# fuse_board.net
KiCad netlist of a schematic drawn in EAGLE
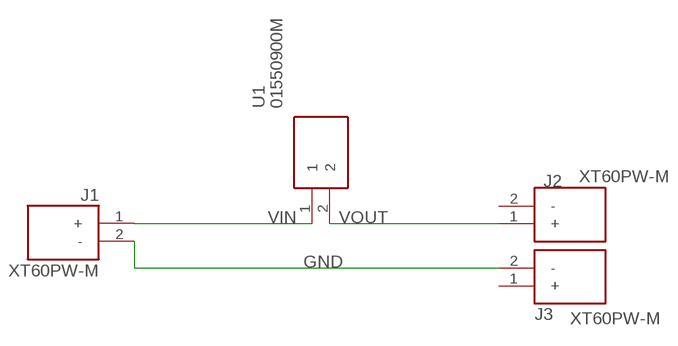
[diagram p0: schematic, sheet 1]

(export (version "E")
  (design (tool "Eeschema 10.0.6"))
  (components
    (comp (ref "J1")
      (value "XT60PW-M")
      (footprint "eagle-import:AMASS_XT60PW-M")
      (fields (field (name "MF") "AMASS"))
      (libsource (lib "eagle-import") (part "XT60PW-M"))
    )
    (comp (ref "J2")
      (value "XT60PW-M")
      (footprint "eagle-import:AMASS_XT60PW-M")
      (fields (field (name "MF") "AMASS"))
      (libsource (lib "eagle-import") (part "XT60PW-M"))
    )
    (comp (ref "J3")
      (value "XT60PW-M")
      (footprint "eagle-import:AMASS_XT60PW-M")
      (fields (field (name "MF") "AMASS"))
      (libsource (lib "eagle-import") (part "XT60PW-M"))
    )
    (comp (ref "U1")
      (value "01550900M")
      (footprint "eagle-import:0154.250DR")
      (fields (field (name "MOUSER_PART_NUMBER") "576-01550900M"))
      (libsource (lib "eagle-import") (part "01550900M"))
    )
  )
  (nets
    (net (code "1") (name "/GND") (class "Default")
      (node (ref "J1") (pin "2") (pinfunction "-_2") (pintype "passive"))
      (node (ref "J3") (pin "2") (pinfunction "-_2") (pintype "passive"))
    )
    (net (code "2") (name "/VIN") (class "Default")
      (node (ref "J1") (pin "1") (pinfunction "+_1") (pintype "passive"))
      (node (ref "U1") (pin "1") (pinfunction "1_1") (pintype "bidirectional"))
    )
    (net (code "3") (name "/VOUT") (class "Default")
      (node (ref "J2") (pin "1") (pinfunction "+_1") (pintype "passive"))
      (node (ref "U1") (pin "2") (pinfunction "2_2") (pintype "bidirectional"))
    )
    (net (code "4") (name "unconnected-(J2---Pad2)") (class "Default")
      (node (ref "J2") (pin "2") (pinfunction "-_2") (pintype "passive"))
    )
    (net (code "5") (name "unconnected-(J3-+-Pad1)") (class "Default")
      (node (ref "J3") (pin "1") (pinfunction "+_1") (pintype "passive"))
    )
  )
)
